# big_seven_control_v0_2.net
KiCad netlist of a schematic drawn in EAGLE
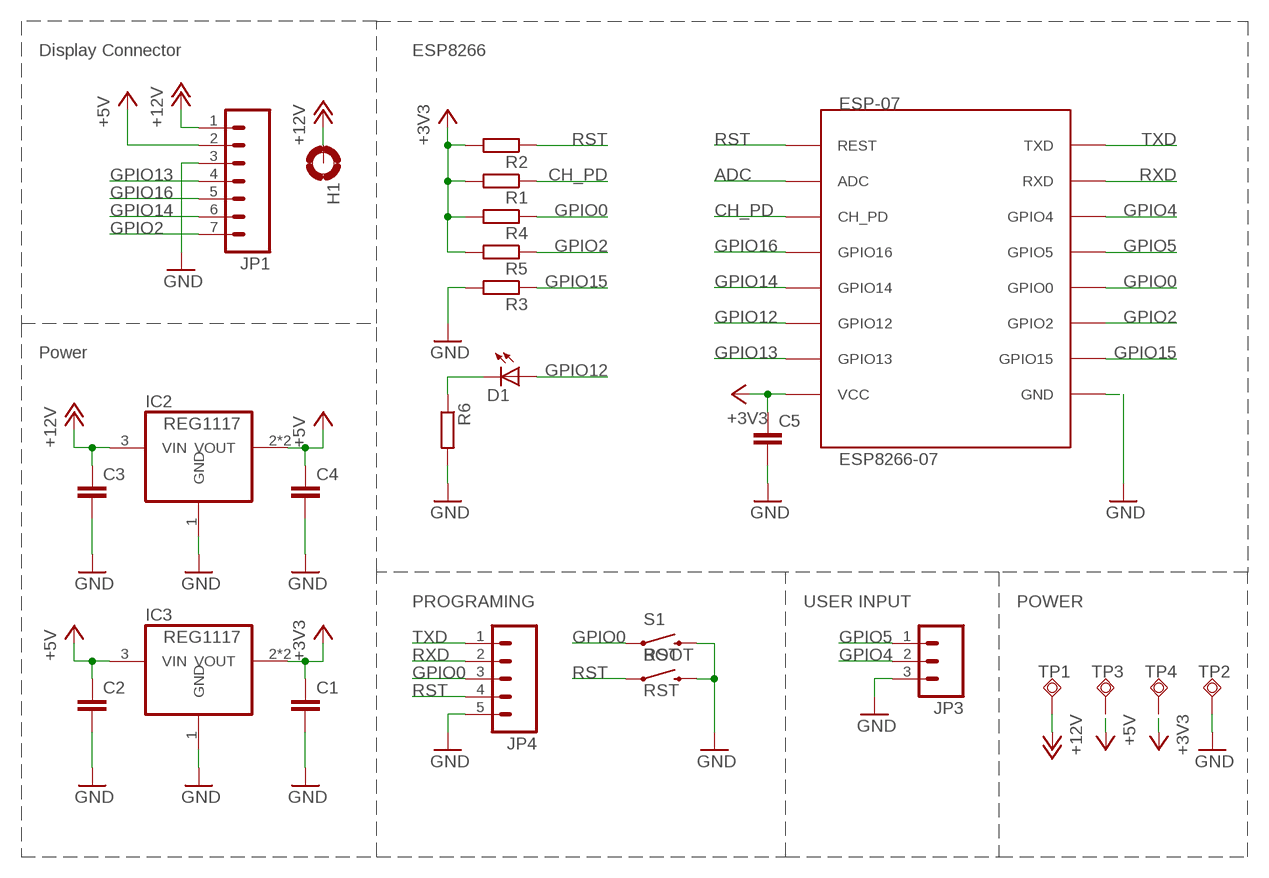
[diagram p0: schematic, sheet 1]

(export (version "E")
  (design (tool "Eeschema 10.0.6"))
  (components
    (comp (ref "C1")
      (value "C-EUC1206K")
      (footprint "eagle-import:C1206K")
      (libsource (lib "eagle-import") (part "C-EUC1206K"))
    )
    (comp (ref "C2")
      (value "C-EUC1206K")
      (footprint "eagle-import:C1206K")
      (libsource (lib "eagle-import") (part "C-EUC1206K"))
    )
    (comp (ref "C3")
      (value "C-EUC1206K")
      (footprint "eagle-import:C1206K")
      (libsource (lib "eagle-import") (part "C-EUC1206K"))
    )
    (comp (ref "C4")
      (value "C-EUC1206K")
      (footprint "eagle-import:C1206K")
      (libsource (lib "eagle-import") (part "C-EUC1206K"))
    )
    (comp (ref "C5")
      (value "C-EUC0805")
      (footprint "eagle-import:C0805")
      (libsource (lib "eagle-import") (part "C-EUC0805"))
    )
    (comp (ref "D1")
      (value "LEDCHIP-LED0805")
      (footprint "eagle-import:CHIP-LED0805")
      (libsource (lib "eagle-import") (part "LEDCHIP-LED0805"))
    )
    (comp (ref "ESP-07")
      (value "ESP8266-07")
      (footprint "eagle-import:ESP-07")
      (libsource (lib "eagle-import") (part "ESP8266-07"))
    )
    (comp (ref "H1")
      (value "MOUNT-PAD-ROUND3.2")
      (footprint "eagle-import:3,2-PAD")
      (libsource (lib "eagle-import") (part "MOUNT-PAD-ROUND3.2"))
    )
    (comp (ref "IC2")
      (value "REG1117")
      (footprint "eagle-import:SOT223")
      (libsource (lib "eagle-import") (part "REG1117"))
    )
    (comp (ref "IC3")
      (value "REG1117")
      (footprint "eagle-import:SOT223")
      (libsource (lib "eagle-import") (part "REG1117"))
    )
    (comp (ref "JP1")
      (value "M07LOCK")
      (footprint "eagle-import:1X07_LOCK")
      (libsource (lib "eagle-import") (part "M07LOCK"))
    )
    (comp (ref "JP3")
      (value "M03LOCK")
      (footprint "eagle-import:1X03_LOCK")
      (libsource (lib "eagle-import") (part "M03LOCK"))
    )
    (comp (ref "JP4")
      (value "M05LOCK")
      (footprint "eagle-import:1X05_LOCK")
      (libsource (lib "eagle-import") (part "M05LOCK"))
    )
    (comp (ref "R1")
      (value "R-EU_R0805")
      (footprint "eagle-import:R0805")
      (libsource (lib "eagle-import") (part "R-EU_R0805"))
    )
    (comp (ref "R2")
      (value "R-EU_R0805")
      (footprint "eagle-import:R0805")
      (libsource (lib "eagle-import") (part "R-EU_R0805"))
    )
    (comp (ref "R3")
      (value "R-EU_R0805")
      (footprint "eagle-import:R0805")
      (libsource (lib "eagle-import") (part "R-EU_R0805"))
    )
    (comp (ref "R4")
      (value "R-EU_R0805")
      (footprint "eagle-import:R0805")
      (libsource (lib "eagle-import") (part "R-EU_R0805"))
    )
    (comp (ref "R5")
      (value "R-EU_R0805")
      (footprint "eagle-import:R0805")
      (libsource (lib "eagle-import") (part "R-EU_R0805"))
    )
    (comp (ref "R6")
      (value "R-EU_R0805")
      (footprint "eagle-import:R0805")
      (libsource (lib "eagle-import") (part "R-EU_R0805"))
    )
    (comp (ref "RST")
      (value "RST")
      (footprint "eagle-import:TACTILE-SWITCH-SMD")
      (libsource (lib "eagle-import") (part "SWITCH-MOMENTARY-2SMD"))
    )
    (comp (ref "S1")
      (value "BOOT")
      (footprint "eagle-import:TACTILE-SWITCH-SMD")
      (libsource (lib "eagle-import") (part "SWITCH-MOMENTARY-2SMD"))
    )
    (comp (ref "TP1")
      (value "12V")
      (footprint "eagle-import:TP20R")
      (libsource (lib "eagle-import") (part "TPSQTP20R"))
    )
    (comp (ref "TP2")
      (value "delk")
      (footprint "eagle-import:TP20R")
      (libsource (lib "eagle-import") (part "TPSQTP20R"))
    )
    (comp (ref "TP3")
      (value "5V")
      (footprint "eagle-import:TP20R")
      (libsource (lib "eagle-import") (part "TPSQTP20R"))
    )
    (comp (ref "TP4")
      (value "3V3")
      (footprint "eagle-import:TP20R")
      (libsource (lib "eagle-import") (part "TPSQTP20R"))
    )
  )
  (nets
    (net (code "1") (name "+3V3") (class "Default")
      (node (ref "C1") (pin "1") (pinfunction "1_1") (pintype "passive"))
      (node (ref "C5") (pin "1") (pinfunction "1_1") (pintype "passive"))
      (node (ref "ESP-07") (pin "VCC") (pinfunction "VCC_VCC") (pintype "power_in"))
      (node (ref "IC3") (pin "2") (pinfunction "VOUT_2") (pintype "output"))
      (node (ref "IC3") (pin "4") (pinfunction "VOUT_4") (pintype "output"))
      (node (ref "R1") (pin "2") (pinfunction "2_2") (pintype "passive"))
      (node (ref "R2") (pin "2") (pinfunction "2_2") (pintype "passive"))
      (node (ref "R4") (pin "2") (pinfunction "2_2") (pintype "passive"))
      (node (ref "R5") (pin "2") (pinfunction "2_2") (pintype "passive"))
      (node (ref "TP4") (pin "TP") (pinfunction "TP_TP") (pintype "input"))
    )
    (net (code "2") (name "+5V") (class "Default")
      (node (ref "C2") (pin "1") (pinfunction "1_1") (pintype "passive"))
      (node (ref "C4") (pin "1") (pinfunction "1_1") (pintype "passive"))
      (node (ref "IC2") (pin "2") (pinfunction "VOUT_2") (pintype "output"))
      (node (ref "IC2") (pin "4") (pinfunction "VOUT_4") (pintype "output"))
      (node (ref "IC3") (pin "3") (pinfunction "VIN_3") (pintype "input"))
      (node (ref "JP1") (pin "2") (pinfunction "2_2") (pintype "passive"))
      (node (ref "TP3") (pin "TP") (pinfunction "TP_TP") (pintype "input"))
    )
    (net (code "3") (name "+12V") (class "Default")
      (node (ref "C3") (pin "1") (pinfunction "1_1") (pintype "passive"))
      (node (ref "H1") (pin "B3,2") (pinfunction "MOUNT_B3,2") (pintype "passive"))
      (node (ref "IC2") (pin "3") (pinfunction "VIN_3") (pintype "input"))
      (node (ref "JP1") (pin "1") (pinfunction "1_1") (pintype "passive"))
      (node (ref "TP1") (pin "TP") (pinfunction "TP_TP") (pintype "input"))
    )
    (net (code "4") (name "/ADC") (class "Default")
      (node (ref "ESP-07") (pin "ADC") (pinfunction "ADC_ADC") (pintype "bidirectional"))
    )
    (net (code "5") (name "/CH_PD") (class "Default")
      (node (ref "ESP-07") (pin "CH_PD") (pinfunction "CH_PD_CH_PD") (pintype "input"))
      (node (ref "R1") (pin "1") (pinfunction "1_1") (pintype "passive"))
    )
    (net (code "6") (name "/GPIO0") (class "Default")
      (node (ref "ESP-07") (pin "GPIO0") (pinfunction "GPIO0_GPIO0") (pintype "bidirectional"))
      (node (ref "JP4") (pin "3") (pinfunction "3_3") (pintype "passive"))
      (node (ref "R4") (pin "1") (pinfunction "1_1") (pintype "passive"))
      (node (ref "S1") (pin "1") (pinfunction "1_1") (pintype "passive"))
    )
    (net (code "7") (name "/GPIO2") (class "Default")
      (node (ref "ESP-07") (pin "GPIO2") (pinfunction "GPIO2_GPIO2") (pintype "bidirectional"))
      (node (ref "JP1") (pin "7") (pinfunction "7_7") (pintype "passive"))
      (node (ref "R5") (pin "1") (pinfunction "1_1") (pintype "passive"))
    )
    (net (code "8") (name "/GPIO4") (class "Default")
      (node (ref "ESP-07") (pin "GPIO4") (pinfunction "GPIO4_GPIO4") (pintype "bidirectional"))
      (node (ref "JP3") (pin "2") (pinfunction "2_2") (pintype "passive"))
    )
    (net (code "9") (name "/GPIO5") (class "Default")
      (node (ref "ESP-07") (pin "GPIO5") (pinfunction "GPIO5_GPIO5") (pintype "bidirectional"))
      (node (ref "JP3") (pin "1") (pinfunction "1_1") (pintype "passive"))
    )
    (net (code "10") (name "/GPIO12") (class "Default")
      (node (ref "D1") (pin "A") (pinfunction "A_A") (pintype "passive"))
      (node (ref "ESP-07") (pin "GPIO12") (pinfunction "GPIO12_GPIO12") (pintype "bidirectional"))
    )
    (net (code "11") (name "/GPIO13") (class "Default")
      (node (ref "ESP-07") (pin "GPIO13") (pinfunction "GPIO13_GPIO13") (pintype "bidirectional"))
      (node (ref "JP1") (pin "4") (pinfunction "4_4") (pintype "passive"))
    )
    (net (code "12") (name "/GPIO14") (class "Default")
      (node (ref "ESP-07") (pin "GPIO14") (pinfunction "GPIO14_GPIO14") (pintype "bidirectional"))
      (node (ref "JP1") (pin "5") (pinfunction "5_5") (pintype "passive"))
    )
    (net (code "13") (name "/GPIO15") (class "Default")
      (node (ref "ESP-07") (pin "GPIO15") (pinfunction "GPIO15_GPIO15") (pintype "input"))
      (node (ref "R3") (pin "1") (pinfunction "1_1") (pintype "passive"))
    )
    (net (code "14") (name "/GPIO16") (class "Default")
      (node (ref "ESP-07") (pin "GPIO16") (pinfunction "GPIO16_GPIO16") (pintype "bidirectional"))
      (node (ref "JP1") (pin "6") (pinfunction "6_6") (pintype "passive"))
    )
    (net (code "15") (name "/RST") (class "Default")
      (node (ref "ESP-07") (pin "REST") (pinfunction "REST_REST") (pintype "bidirectional"))
      (node (ref "JP4") (pin "4") (pinfunction "4_4") (pintype "passive"))
      (node (ref "R2") (pin "1") (pinfunction "1_1") (pintype "passive"))
      (node (ref "RST") (pin "1") (pinfunction "1_1") (pintype "passive"))
    )
    (net (code "16") (name "/RXD") (class "Default")
      (node (ref "ESP-07") (pin "RXD") (pinfunction "RXD_RXD") (pintype "input"))
      (node (ref "JP4") (pin "2") (pinfunction "2_2") (pintype "passive"))
    )
    (net (code "17") (name "/TXD") (class "Default")
      (node (ref "ESP-07") (pin "TXD") (pinfunction "TXD_TXD") (pintype "output"))
      (node (ref "JP4") (pin "1") (pinfunction "1_1") (pintype "passive"))
    )
    (net (code "18") (name "GND") (class "Default")
      (node (ref "C1") (pin "2") (pinfunction "2_2") (pintype "passive"))
      (node (ref "C2") (pin "2") (pinfunction "2_2") (pintype "passive"))
      (node (ref "C3") (pin "2") (pinfunction "2_2") (pintype "passive"))
      (node (ref "C4") (pin "2") (pinfunction "2_2") (pintype "passive"))
      (node (ref "C5") (pin "2") (pinfunction "2_2") (pintype "passive"))
      (node (ref "ESP-07") (pin "GND") (pinfunction "GND_GND") (pintype "power_in"))
      (node (ref "IC2") (pin "1") (pinfunction "GND_1") (pintype "power_in"))
      (node (ref "IC3") (pin "1") (pinfunction "GND_1") (pintype "power_in"))
      (node (ref "JP1") (pin "3") (pinfunction "3_3") (pintype "passive"))
      (node (ref "JP3") (pin "3") (pinfunction "3_3") (pintype "passive"))
      (node (ref "JP4") (pin "5") (pinfunction "5_5") (pintype "passive"))
      (node (ref "R3") (pin "2") (pinfunction "2_2") (pintype "passive"))
      (node (ref "R6") (pin "2") (pinfunction "2_2") (pintype "passive"))
      (node (ref "RST") (pin "3") (pinfunction "2_3") (pintype "passive"))
      (node (ref "S1") (pin "3") (pinfunction "2_3") (pintype "passive"))
      (node (ref "TP2") (pin "TP") (pinfunction "TP_TP") (pintype "input"))
    )
    (net (code "19") (name "Net-(D1-PadC)") (class "Default")
      (node (ref "D1") (pin "C") (pinfunction "C_C") (pintype "passive"))
      (node (ref "R6") (pin "1") (pinfunction "1_1") (pintype "passive"))
    )
  )
)
